# SCH_DroneSlider_Circuit.net
KiCad netlist of a schematic drawn in EasyEDA
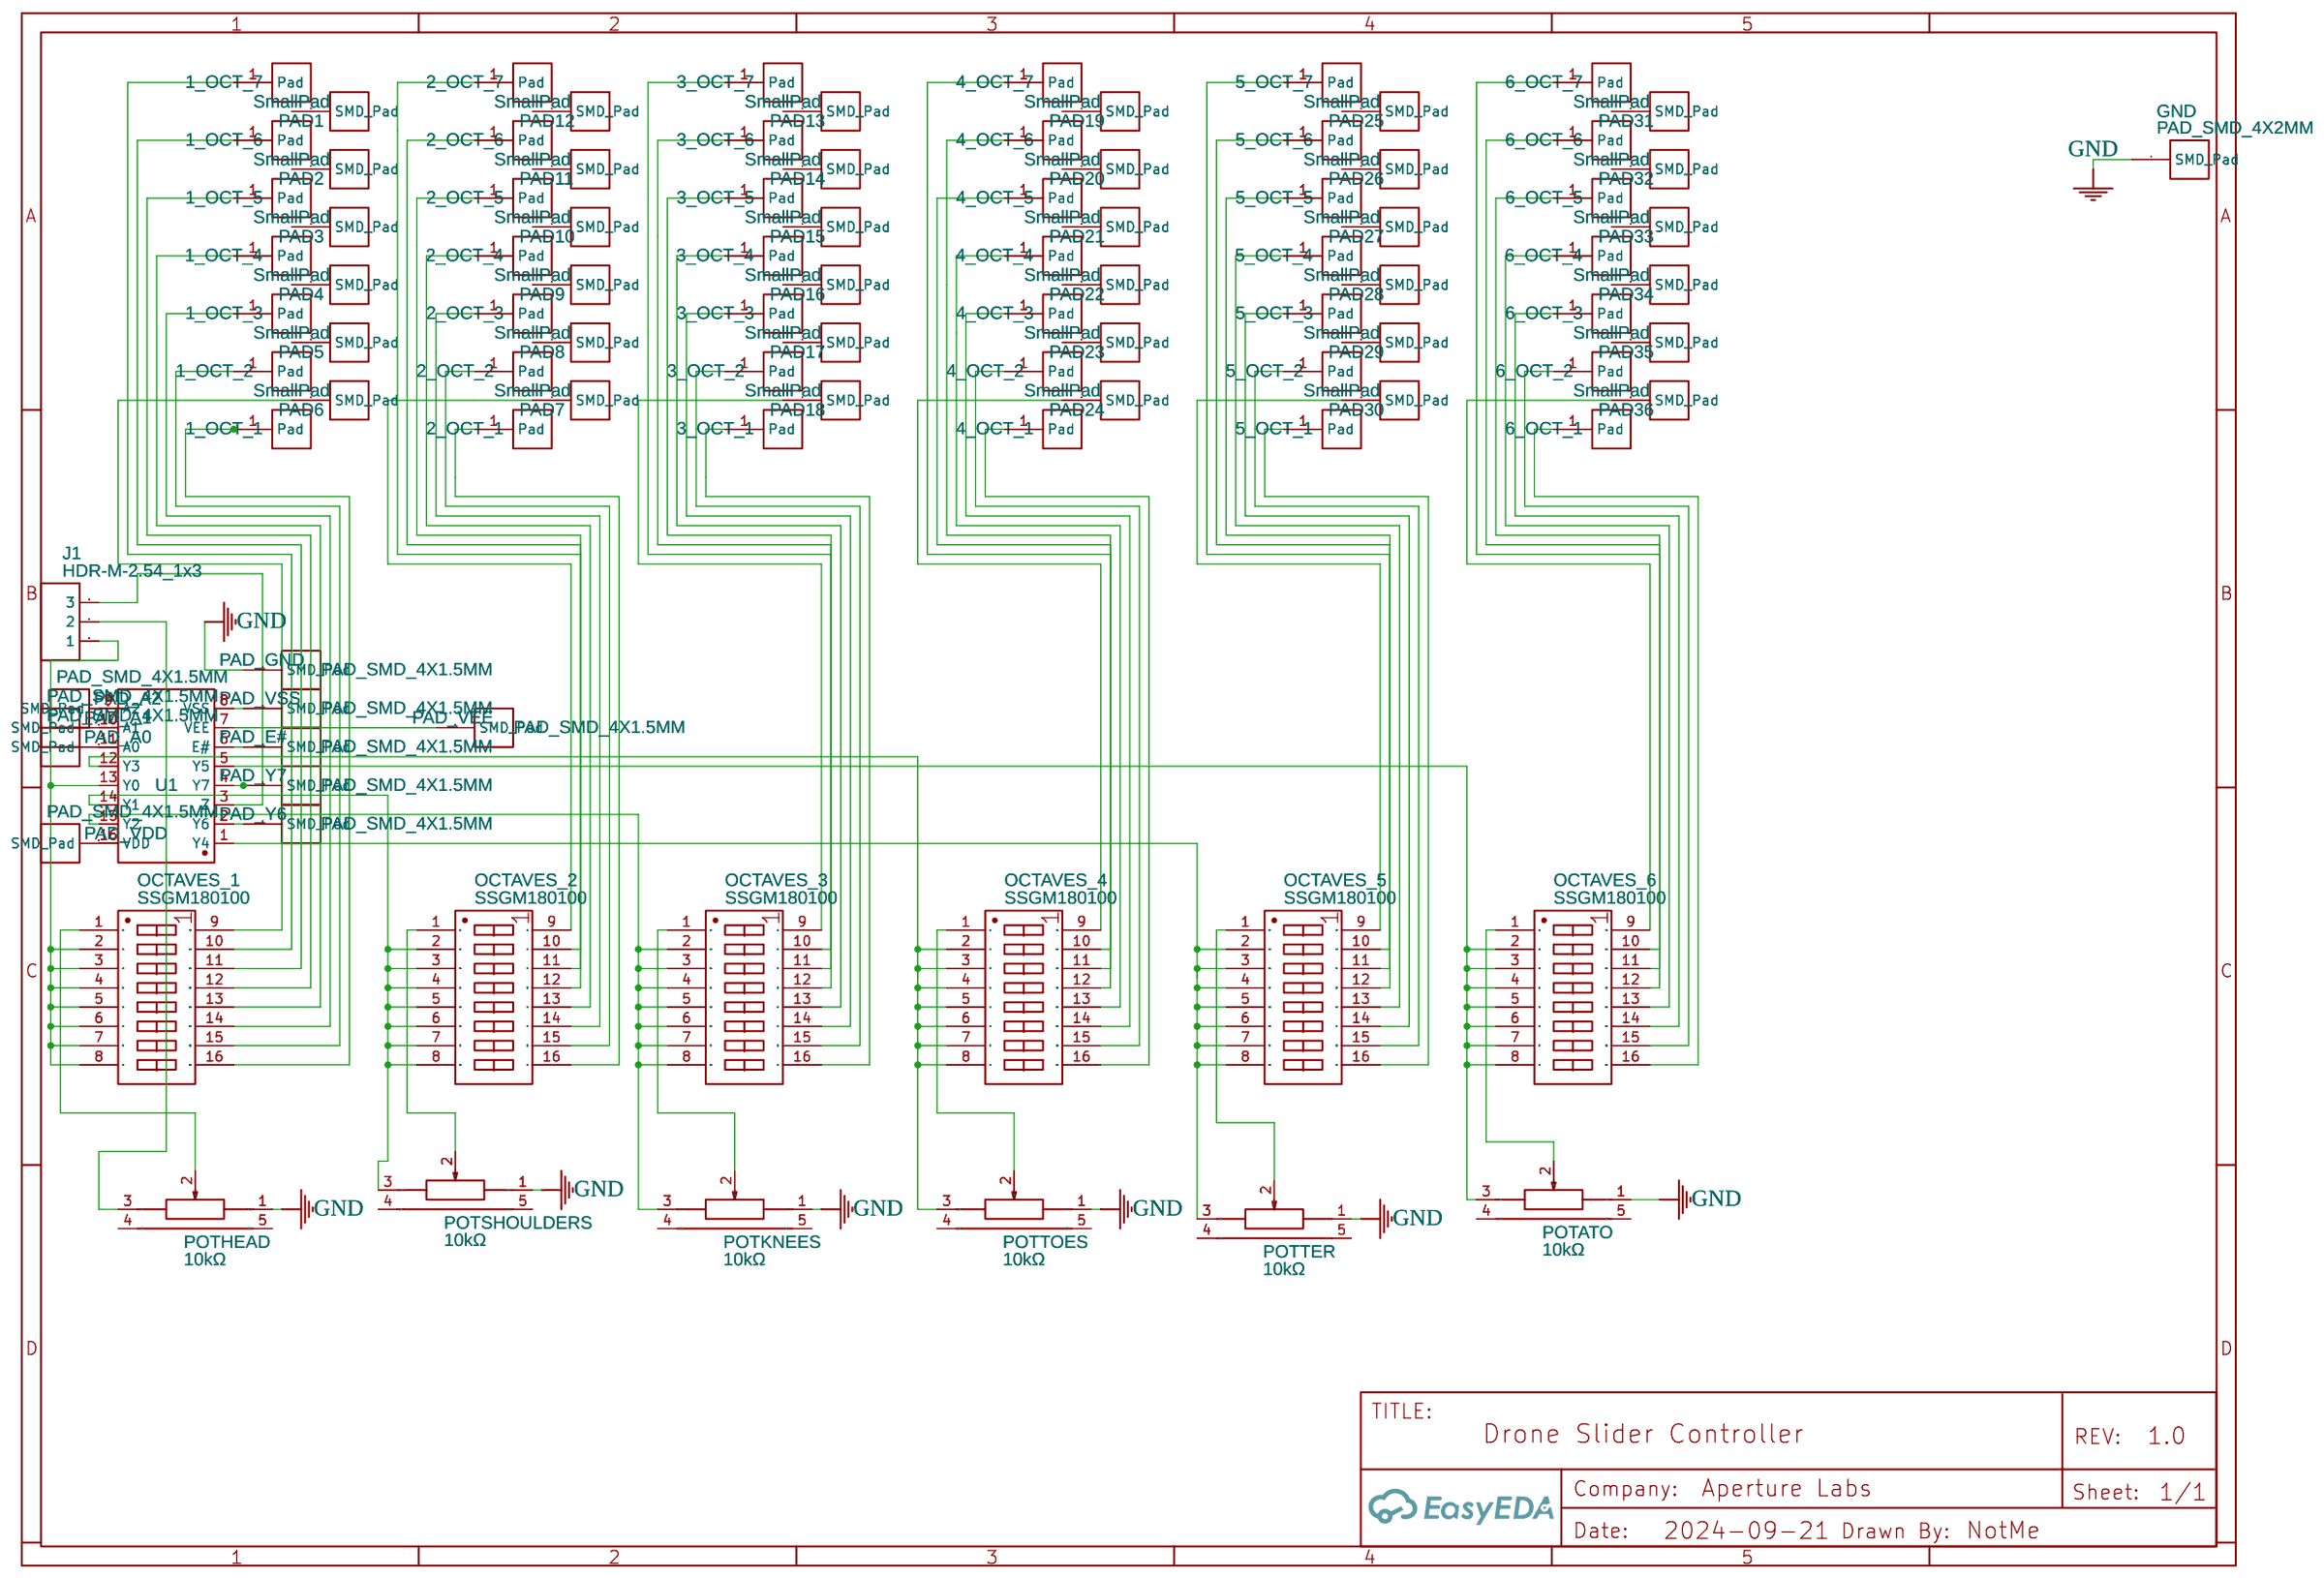
[diagram p0: schematic sheet]

(export (version "E")
  (design (tool "Eeschema 10.0.6"))
  (components
    (comp (ref "1_OCT_1") (value "OCT") (libsource (lib "") (part "PAD_5")))
    (comp (ref "1_OCT_2") (value "OCT") (libsource (lib "") (part "PAD_5")))
    (comp (ref "1_OCT_3") (value "OCT") (libsource (lib "") (part "PAD_5")))
    (comp (ref "1_OCT_4") (value "OCT") (libsource (lib "") (part "PAD_5")))
    (comp (ref "1_OCT_5") (value "OCT") (libsource (lib "") (part "PAD_5")))
    (comp (ref "1_OCT_6") (value "OCT") (libsource (lib "") (part "PAD_5")))
    (comp (ref "1_OCT_7") (value "OCT") (libsource (lib "") (part "PAD_5")))
    (comp (ref "2_OCT_1") (value "OCT") (libsource (lib "") (part "PAD_2")))
    (comp (ref "2_OCT_2") (value "OCT") (libsource (lib "") (part "PAD_2")))
    (comp (ref "2_OCT_3") (value "OCT") (libsource (lib "") (part "PAD_2")))
    (comp (ref "2_OCT_4") (value "OCT") (libsource (lib "") (part "PAD_2")))
    (comp (ref "2_OCT_5") (value "OCT") (libsource (lib "") (part "PAD_2")))
    (comp (ref "2_OCT_6") (value "OCT") (libsource (lib "") (part "PAD_2")))
    (comp (ref "2_OCT_7") (value "OCT") (libsource (lib "") (part "PAD_2")))
    (comp (ref "3_OCT_1") (value "OCT") (libsource (lib "") (part "PAD_3")))
    (comp (ref "3_OCT_2") (value "OCT") (libsource (lib "") (part "PAD_3")))
    (comp (ref "3_OCT_3") (value "OCT") (libsource (lib "") (part "PAD_3")))
    (comp (ref "3_OCT_4") (value "OCT") (libsource (lib "") (part "PAD_3")))
    (comp (ref "3_OCT_5") (value "OCT") (libsource (lib "") (part "PAD_3")))
    (comp (ref "3_OCT_6") (value "OCT") (libsource (lib "") (part "PAD_3")))
    (comp (ref "3_OCT_7") (value "OCT") (libsource (lib "") (part "PAD_3")))
    (comp (ref "4_OCT_1") (value "OCT") (libsource (lib "") (part "PAD_4")))
    (comp (ref "4_OCT_2") (value "OCT") (libsource (lib "") (part "PAD_4")))
    (comp (ref "4_OCT_3") (value "OCT") (libsource (lib "") (part "PAD_4")))
    (comp (ref "4_OCT_4") (value "OCT") (libsource (lib "") (part "PAD_4")))
    (comp (ref "4_OCT_5") (value "OCT") (libsource (lib "") (part "PAD_4")))
    (comp (ref "4_OCT_6") (value "OCT") (libsource (lib "") (part "PAD_4")))
    (comp (ref "4_OCT_7") (value "OCT") (libsource (lib "") (part "PAD_4")))
    (comp (ref "5_OCT_1") (value "OCT") (libsource (lib "") (part "PAD")))
    (comp (ref "5_OCT_2") (value "OCT") (libsource (lib "") (part "PAD")))
    (comp (ref "5_OCT_3") (value "OCT") (libsource (lib "") (part "PAD")))
    (comp (ref "5_OCT_4") (value "OCT") (libsource (lib "") (part "PAD")))
    (comp (ref "5_OCT_5") (value "OCT") (libsource (lib "") (part "PAD")))
    (comp (ref "5_OCT_6") (value "OCT") (libsource (lib "") (part "PAD")))
    (comp (ref "5_OCT_7") (value "OCT") (libsource (lib "") (part "PAD")))
    (comp (ref "6_OCT_1") (value "OCT") (libsource (lib "") (part "PAD_1")))
    (comp (ref "6_OCT_2") (value "OCT") (libsource (lib "") (part "PAD_1")))
    (comp (ref "6_OCT_3") (value "OCT") (libsource (lib "") (part "PAD_1")))
    (comp (ref "6_OCT_4") (value "OCT") (libsource (lib "") (part "PAD_1")))
    (comp (ref "6_OCT_5") (value "OCT") (libsource (lib "") (part "PAD_1")))
    (comp (ref "6_OCT_6") (value "OCT") (libsource (lib "") (part "PAD_1")))
    (comp (ref "6_OCT_7") (value "OCT") (libsource (lib "") (part "PAD_1")))
    (comp (ref "GND") (value "PAD_SMD_4X2MM") (libsource (lib "") (part "PAD_SMD_4X2MM")))
    (comp (ref "J1") (value "HDR-M-2.54_1x3") (libsource (lib "") (part "HDR-M-2.54_1x3")))
    (comp (ref "OCTAVES_1")
      (value "SSGM180100")
      (fields (field (name "Manufacturer") "ALPSALPINE(阿尔卑斯阿尔派)"))
      (libsource (lib "") (part "SSGM180100"))
    )
    (comp (ref "OCTAVES_2")
      (value "SSGM180100")
      (fields (field (name "Manufacturer") "ALPSALPINE(阿尔卑斯阿尔派)"))
      (libsource (lib "") (part "SSGM180100"))
    )
    (comp (ref "OCTAVES_3")
      (value "SSGM180100")
      (fields (field (name "Manufacturer") "ALPSALPINE(阿尔卑斯阿尔派)"))
      (libsource (lib "") (part "SSGM180100"))
    )
    (comp (ref "OCTAVES_4")
      (value "SSGM180100")
      (fields (field (name "Manufacturer") "ALPSALPINE(阿尔卑斯阿尔派)"))
      (libsource (lib "") (part "SSGM180100"))
    )
    (comp (ref "OCTAVES_5")
      (value "SSGM180100")
      (fields (field (name "Manufacturer") "ALPSALPINE(阿尔卑斯阿尔派)"))
      (libsource (lib "") (part "SSGM180100"))
    )
    (comp (ref "OCTAVES_6")
      (value "SSGM180100")
      (fields (field (name "Manufacturer") "ALPSALPINE(阿尔卑斯阿尔派)"))
      (libsource (lib "") (part "SSGM180100"))
    )
    (comp (ref "PAD1") (value "SmallPad") (libsource (lib "") (part "PAD_SMD_4X1.5MM")))
    (comp (ref "PAD2") (value "SmallPad") (libsource (lib "") (part "PAD_SMD_4X1.5MM")))
    (comp (ref "PAD3") (value "SmallPad") (libsource (lib "") (part "PAD_SMD_4X1.5MM")))
    (comp (ref "PAD4") (value "SmallPad") (libsource (lib "") (part "PAD_SMD_4X1.5MM")))
    (comp (ref "PAD5") (value "SmallPad") (libsource (lib "") (part "PAD_SMD_4X1.5MM")))
    (comp (ref "PAD6") (value "SmallPad") (libsource (lib "") (part "PAD_SMD_4X1.5MM")))
    (comp (ref "PAD7") (value "SmallPad") (libsource (lib "") (part "PAD_SMD_4X1.5MM")))
    (comp (ref "PAD8") (value "SmallPad") (libsource (lib "") (part "PAD_SMD_4X1.5MM")))
    (comp (ref "PAD9") (value "SmallPad") (libsource (lib "") (part "PAD_SMD_4X1.5MM")))
    (comp (ref "PAD10") (value "SmallPad") (libsource (lib "") (part "PAD_SMD_4X1.5MM")))
    (comp (ref "PAD11") (value "SmallPad") (libsource (lib "") (part "PAD_SMD_4X1.5MM")))
    (comp (ref "PAD12") (value "SmallPad") (libsource (lib "") (part "PAD_SMD_4X1.5MM")))
    (comp (ref "PAD13") (value "SmallPad") (libsource (lib "") (part "PAD_SMD_4X1.5MM")))
    (comp (ref "PAD14") (value "SmallPad") (libsource (lib "") (part "PAD_SMD_4X1.5MM")))
    (comp (ref "PAD15") (value "SmallPad") (libsource (lib "") (part "PAD_SMD_4X1.5MM")))
    (comp (ref "PAD16") (value "SmallPad") (libsource (lib "") (part "PAD_SMD_4X1.5MM")))
    (comp (ref "PAD17") (value "SmallPad") (libsource (lib "") (part "PAD_SMD_4X1.5MM")))
    (comp (ref "PAD18") (value "SmallPad") (libsource (lib "") (part "PAD_SMD_4X1.5MM")))
    (comp (ref "PAD19") (value "SmallPad") (libsource (lib "") (part "PAD_SMD_4X1.5MM")))
    (comp (ref "PAD20") (value "SmallPad") (libsource (lib "") (part "PAD_SMD_4X1.5MM")))
    (comp (ref "PAD21") (value "SmallPad") (libsource (lib "") (part "PAD_SMD_4X1.5MM")))
    (comp (ref "PAD22") (value "SmallPad") (libsource (lib "") (part "PAD_SMD_4X1.5MM")))
    (comp (ref "PAD23") (value "SmallPad") (libsource (lib "") (part "PAD_SMD_4X1.5MM")))
    (comp (ref "PAD24") (value "SmallPad") (libsource (lib "") (part "PAD_SMD_4X1.5MM")))
    (comp (ref "PAD25") (value "SmallPad") (libsource (lib "") (part "PAD_SMD_4X1.5MM")))
    (comp (ref "PAD26") (value "SmallPad") (libsource (lib "") (part "PAD_SMD_4X1.5MM")))
    (comp (ref "PAD27") (value "SmallPad") (libsource (lib "") (part "PAD_SMD_4X1.5MM")))
    (comp (ref "PAD28") (value "SmallPad") (libsource (lib "") (part "PAD_SMD_4X1.5MM")))
    (comp (ref "PAD29") (value "SmallPad") (libsource (lib "") (part "PAD_SMD_4X1.5MM")))
    (comp (ref "PAD30") (value "SmallPad") (libsource (lib "") (part "PAD_SMD_4X1.5MM")))
    (comp (ref "PAD31") (value "SmallPad") (libsource (lib "") (part "PAD_SMD_4X1.5MM")))
    (comp (ref "PAD32") (value "SmallPad") (libsource (lib "") (part "PAD_SMD_4X1.5MM")))
    (comp (ref "PAD33") (value "SmallPad") (libsource (lib "") (part "PAD_SMD_4X1.5MM")))
    (comp (ref "PAD34") (value "SmallPad") (libsource (lib "") (part "PAD_SMD_4X1.5MM")))
    (comp (ref "PAD35") (value "SmallPad") (libsource (lib "") (part "PAD_SMD_4X1.5MM")))
    (comp (ref "PAD36") (value "SmallPad") (libsource (lib "") (part "PAD_SMD_4X1.5MM")))
    (comp (ref "PAD_A0") (value "PAD_SMD_4X1.5MM") (libsource (lib "") (part "PAD_SMD_4X1.5MM_2")))
    (comp (ref "PAD_A1") (value "PAD_SMD_4X1.5MM") (libsource (lib "") (part "PAD_SMD_4X1.5MM_2")))
    (comp (ref "PAD_A2") (value "PAD_SMD_4X1.5MM") (libsource (lib "") (part "PAD_SMD_4X1.5MM_2")))
    (comp (ref "PAD_E#") (value "PAD_SMD_4X1.5MM") (libsource (lib "") (part "PAD_SMD_4X1.5MM_1")))
    (comp (ref "PAD_GND") (value "PAD_SMD_4X1.5MM") (libsource (lib "") (part "PAD_SMD_4X1.5MM_4")))
    (comp (ref "PAD_VDD") (value "PAD_SMD_4X1.5MM") (libsource (lib "") (part "PAD_SMD_4X1.5MM_7")))
    (comp (ref "PAD_VEE") (value "PAD_SMD_4X1.5MM") (libsource (lib "") (part "PAD_SMD_4X1.5MM_6")))
    (comp (ref "PAD_VSS") (value "PAD_SMD_4X1.5MM") (libsource (lib "") (part "PAD_SMD_4X1.5MM_5")))
    (comp (ref "PAD_Y6") (value "PAD_SMD_4X1.5MM") (libsource (lib "") (part "PAD_SMD_4X1.5MM_3")))
    (comp (ref "PAD_Y7") (value "PAD_SMD_4X1.5MM") (libsource (lib "") (part "PAD_SMD_4X1.5MM_3")))
    (comp (ref "POTATO")
      (value "10kΩ")
      (fields
        (field (name "Manufacturer Part") "RK09K1130A5R")
        (field (name "Manufacturer") "ALPSALPINE(阿尔卑斯阿尔派)")
      )
      (libsource (lib "") (part "RK09K1130A5R_1"))
    )
    (comp (ref "POTHEAD")
      (value "10kΩ")
      (fields
        (field (name "Manufacturer Part") "RK09K1130A5R")
        (field (name "Manufacturer") "ALPSALPINE(阿尔卑斯阿尔派)")
      )
      (libsource (lib "") (part "RK09K1130A5R_2"))
    )
    (comp (ref "POTKNEES")
      (value "10kΩ")
      (fields
        (field (name "Manufacturer Part") "RK09K1130A5R")
        (field (name "Manufacturer") "ALPSALPINE(阿尔卑斯阿尔派)")
      )
      (libsource (lib "") (part "RK09K1130A5R"))
    )
    (comp (ref "POTSHOULDERS")
      (value "10kΩ")
      (fields
        (field (name "Manufacturer Part") "RK09K1130A5R")
        (field (name "Manufacturer") "ALPSALPINE(阿尔卑斯阿尔派)")
      )
      (libsource (lib "") (part "RK09K1130A5R_3"))
    )
    (comp (ref "POTTER")
      (value "10kΩ")
      (fields
        (field (name "Manufacturer Part") "RK09K1130A5R")
        (field (name "Manufacturer") "ALPSALPINE(阿尔卑斯阿尔派)")
      )
      (libsource (lib "") (part "RK09K1130A5R_4"))
    )
    (comp (ref "POTTOES")
      (value "10kΩ")
      (fields
        (field (name "Manufacturer Part") "RK09K1130A5R")
        (field (name "Manufacturer") "ALPSALPINE(阿尔卑斯阿尔派)")
      )
      (libsource (lib "") (part "RK09K1130A5R_5"))
    )
    (comp (ref "U1")
      (value "CD4051BE_C507164")
      (fields (field (name "Manufacturer Part") "CD4051BE") (field (name "Manufacturer") "HGSEMI(华冠)"))
      (libsource (lib "") (part "CD4051BE_C507164"))
    )
  )
  (nets
    (net (code "1") (name "GND") (class "Default")
      (node (ref "GND") (pin "1") (pinfunction "SMD_Pad_1") (pintype "unspecified"))
      (node (ref "PAD_GND") (pin "1") (pinfunction "SMD_Pad_1") (pintype "unspecified"))
      (node (ref "POTATO") (pin "1") (pinfunction "1_1") (pintype "unspecified"))
      (node (ref "POTHEAD") (pin "1") (pinfunction "1_1") (pintype "unspecified"))
      (node (ref "POTKNEES") (pin "1") (pinfunction "1_1") (pintype "unspecified"))
      (node (ref "POTSHOULDERS") (pin "1") (pinfunction "1_1") (pintype "unspecified"))
      (node (ref "POTTER") (pin "1") (pinfunction "1_1") (pintype "unspecified"))
      (node (ref "POTTOES") (pin "1") (pinfunction "1_1") (pintype "unspecified"))
    )
    (net (code "2") (name "Net-(1_OCT_1-Pad)") (class "Default")
      (node (ref "1_OCT_1") (pin "1") (pinfunction "Pad_1") (pintype "unspecified"))
      (node (ref "OCTAVES_1") (pin "16") (pinfunction "PIN16_16") (pintype "unspecified"))
    )
    (net (code "3") (name "Net-(1_OCT_2-Pad)") (class "Default")
      (node (ref "1_OCT_2") (pin "1") (pinfunction "Pad_1") (pintype "unspecified"))
      (node (ref "OCTAVES_1") (pin "15") (pinfunction "PIN16_15") (pintype "unspecified"))
    )
    (net (code "4") (name "Net-(2_OCT_1-Pad)") (class "Default")
      (node (ref "2_OCT_1") (pin "1") (pinfunction "Pad_1") (pintype "unspecified"))
      (node (ref "OCTAVES_2") (pin "16") (pinfunction "PIN16_16") (pintype "unspecified"))
    )
    (net (code "5") (name "Net-(2_OCT_2-Pad)") (class "Default")
      (node (ref "2_OCT_2") (pin "1") (pinfunction "Pad_1") (pintype "unspecified"))
      (node (ref "OCTAVES_2") (pin "15") (pinfunction "PIN16_15") (pintype "unspecified"))
    )
    (net (code "6") (name "Net-(3_OCT_1-Pad)") (class "Default")
      (node (ref "3_OCT_1") (pin "1") (pinfunction "Pad_1") (pintype "unspecified"))
      (node (ref "OCTAVES_3") (pin "16") (pinfunction "PIN16_16") (pintype "unspecified"))
    )
    (net (code "7") (name "Net-(3_OCT_2-Pad)") (class "Default")
      (node (ref "3_OCT_2") (pin "1") (pinfunction "Pad_1") (pintype "unspecified"))
      (node (ref "OCTAVES_3") (pin "15") (pinfunction "PIN16_15") (pintype "unspecified"))
    )
    (net (code "8") (name "Net-(4_OCT_1-Pad)") (class "Default")
      (node (ref "4_OCT_1") (pin "1") (pinfunction "Pad_1") (pintype "unspecified"))
      (node (ref "OCTAVES_4") (pin "16") (pinfunction "PIN16_16") (pintype "unspecified"))
    )
    (net (code "9") (name "Net-(4_OCT_2-Pad)") (class "Default")
      (node (ref "4_OCT_2") (pin "1") (pinfunction "Pad_1") (pintype "unspecified"))
      (node (ref "OCTAVES_4") (pin "15") (pinfunction "PIN16_15") (pintype "unspecified"))
    )
    (net (code "10") (name "Net-(5_OCT_1-Pad)") (class "Default")
      (node (ref "5_OCT_1") (pin "1") (pinfunction "Pad_1") (pintype "unspecified"))
      (node (ref "OCTAVES_5") (pin "16") (pinfunction "PIN16_16") (pintype "unspecified"))
    )
    (net (code "11") (name "Net-(5_OCT_2-Pad)") (class "Default")
      (node (ref "5_OCT_2") (pin "1") (pinfunction "Pad_1") (pintype "unspecified"))
      (node (ref "OCTAVES_5") (pin "15") (pinfunction "PIN16_15") (pintype "unspecified"))
    )
    (net (code "12") (name "Net-(6_OCT_1-Pad)") (class "Default")
      (node (ref "6_OCT_1") (pin "1") (pinfunction "Pad_1") (pintype "unspecified"))
      (node (ref "OCTAVES_6") (pin "16") (pinfunction "PIN16_16") (pintype "unspecified"))
    )
    (net (code "13") (name "Net-(6_OCT_2-Pad)") (class "Default")
      (node (ref "6_OCT_2") (pin "1") (pinfunction "Pad_1") (pintype "unspecified"))
      (node (ref "OCTAVES_6") (pin "15") (pinfunction "PIN16_15") (pintype "unspecified"))
    )
    (net (code "14") (name "Net-(J1-Pad2)") (class "Default")
      (node (ref "J1") (pin "2") (pinfunction "2_2") (pintype "input"))
      (node (ref "POTHEAD") (pin "3") (pinfunction "3_3") (pintype "unspecified"))
    )
    (net (code "15") (name "Net-(OCTAVES_1-PIN1)") (class "Default")
      (node (ref "OCTAVES_1") (pin "1") (pinfunction "PIN1_1") (pintype "unspecified"))
      (node (ref "POTHEAD") (pin "2") (pinfunction "2_2") (pintype "unspecified"))
    )
    (net (code "16") (name "Net-(OCTAVES_1-PIN2)") (class "Default")
      (node (ref "J1") (pin "1") (pinfunction "1_1") (pintype "input"))
      (node (ref "OCTAVES_1") (pin "2") (pinfunction "PIN2_2") (pintype "unspecified"))
      (node (ref "OCTAVES_1") (pin "3") (pinfunction "PIN3_3") (pintype "unspecified"))
      (node (ref "OCTAVES_1") (pin "4") (pinfunction "PIN4_4") (pintype "unspecified"))
      (node (ref "OCTAVES_1") (pin "5") (pinfunction "PIN5_5") (pintype "unspecified"))
      (node (ref "OCTAVES_1") (pin "6") (pinfunction "PIN6_6") (pintype "unspecified"))
      (node (ref "OCTAVES_1") (pin "7") (pinfunction "PIN7_7") (pintype "unspecified"))
      (node (ref "OCTAVES_1") (pin "8") (pinfunction "PIN8_8") (pintype "unspecified"))
      (node (ref "U1") (pin "13") (pinfunction "Y0_13") (pintype "unspecified"))
    )
    (net (code "17") (name "Net-(OCTAVES_1-PIN9)") (class "Default")
      (node (ref "OCTAVES_1") (pin "9") (pinfunction "PIN9_9") (pintype "unspecified"))
      (node (ref "PAD6") (pin "1") (pinfunction "SMD_Pad_1") (pintype "unspecified"))
    )
    (net (code "18") (name "Net-(OCTAVES_1-PIN10)") (class "Default")
      (node (ref "1_OCT_7") (pin "1") (pinfunction "Pad_1") (pintype "unspecified"))
      (node (ref "OCTAVES_1") (pin "10") (pinfunction "PIN10_10") (pintype "unspecified"))
    )
    (net (code "19") (name "Net-(OCTAVES_1-PIN11)") (class "Default")
      (node (ref "1_OCT_6") (pin "1") (pinfunction "Pad_1") (pintype "unspecified"))
      (node (ref "OCTAVES_1") (pin "11") (pinfunction "PIN11_11") (pintype "unspecified"))
    )
    (net (code "20") (name "Net-(OCTAVES_1-PIN12)") (class "Default")
      (node (ref "1_OCT_5") (pin "1") (pinfunction "Pad_1") (pintype "unspecified"))
      (node (ref "OCTAVES_1") (pin "12") (pinfunction "PIN12_12") (pintype "unspecified"))
    )
    (net (code "21") (name "Net-(OCTAVES_1-PIN13)") (class "Default")
      (node (ref "1_OCT_4") (pin "1") (pinfunction "Pad_1") (pintype "unspecified"))
      (node (ref "OCTAVES_1") (pin "13") (pinfunction "PIN13_13") (pintype "unspecified"))
    )
    (net (code "22") (name "Net-(OCTAVES_1-PIN14)") (class "Default")
      (node (ref "1_OCT_3") (pin "1") (pinfunction "Pad_1") (pintype "unspecified"))
      (node (ref "OCTAVES_1") (pin "14") (pinfunction "PIN14_14") (pintype "unspecified"))
    )
    (net (code "23") (name "Net-(OCTAVES_2-PIN1)") (class "Default")
      (node (ref "OCTAVES_2") (pin "1") (pinfunction "PIN1_1") (pintype "unspecified"))
      (node (ref "POTSHOULDERS") (pin "2") (pinfunction "2_2") (pintype "unspecified"))
    )
    (net (code "24") (name "Net-(OCTAVES_2-PIN2)") (class "Default")
      (node (ref "OCTAVES_2") (pin "2") (pinfunction "PIN2_2") (pintype "unspecified"))
      (node (ref "OCTAVES_2") (pin "3") (pinfunction "PIN3_3") (pintype "unspecified"))
      (node (ref "OCTAVES_2") (pin "4") (pinfunction "PIN4_4") (pintype "unspecified"))
      (node (ref "OCTAVES_2") (pin "5") (pinfunction "PIN5_5") (pintype "unspecified"))
      (node (ref "OCTAVES_2") (pin "6") (pinfunction "PIN6_6") (pintype "unspecified"))
      (node (ref "OCTAVES_2") (pin "7") (pinfunction "PIN7_7") (pintype "unspecified"))
      (node (ref "OCTAVES_2") (pin "8") (pinfunction "PIN8_8") (pintype "unspecified"))
      (node (ref "POTSHOULDERS") (pin "3") (pinfunction "3_3") (pintype "unspecified"))
      (node (ref "U1") (pin "14") (pinfunction "Y1_14") (pintype "unspecified"))
    )
    (net (code "25") (name "Net-(OCTAVES_2-PIN9)") (class "Default")
      (node (ref "OCTAVES_2") (pin "9") (pinfunction "PIN9_9") (pintype "unspecified"))
      (node (ref "PAD7") (pin "1") (pinfunction "SMD_Pad_1") (pintype "unspecified"))
    )
    (net (code "26") (name "Net-(OCTAVES_2-PIN10)") (class "Default")
      (node (ref "2_OCT_7") (pin "1") (pinfunction "Pad_1") (pintype "unspecified"))
      (node (ref "OCTAVES_2") (pin "10") (pinfunction "PIN10_10") (pintype "unspecified"))
    )
    (net (code "27") (name "Net-(OCTAVES_2-PIN11)") (class "Default")
      (node (ref "2_OCT_6") (pin "1") (pinfunction "Pad_1") (pintype "unspecified"))
      (node (ref "OCTAVES_2") (pin "11") (pinfunction "PIN11_11") (pintype "unspecified"))
    )
    (net (code "28") (name "Net-(OCTAVES_2-PIN12)") (class "Default")
      (node (ref "2_OCT_5") (pin "1") (pinfunction "Pad_1") (pintype "unspecified"))
      (node (ref "OCTAVES_2") (pin "12") (pinfunction "PIN12_12") (pintype "unspecified"))
    )
    (net (code "29") (name "Net-(OCTAVES_2-PIN13)") (class "Default")
      (node (ref "2_OCT_4") (pin "1") (pinfunction "Pad_1") (pintype "unspecified"))
      (node (ref "OCTAVES_2") (pin "13") (pinfunction "PIN13_13") (pintype "unspecified"))
    )
    (net (code "30") (name "Net-(OCTAVES_2-PIN14)") (class "Default")
      (node (ref "2_OCT_3") (pin "1") (pinfunction "Pad_1") (pintype "unspecified"))
      (node (ref "OCTAVES_2") (pin "14") (pinfunction "PIN14_14") (pintype "unspecified"))
    )
    (net (code "31") (name "Net-(OCTAVES_3-PIN1)") (class "Default")
      (node (ref "OCTAVES_3") (pin "1") (pinfunction "PIN1_1") (pintype "unspecified"))
      (node (ref "POTKNEES") (pin "2") (pinfunction "2_2") (pintype "unspecified"))
    )
    (net (code "32") (name "Net-(OCTAVES_3-PIN2)") (class "Default")
      (node (ref "OCTAVES_3") (pin "2") (pinfunction "PIN2_2") (pintype "unspecified"))
      (node (ref "OCTAVES_3") (pin "3") (pinfunction "PIN3_3") (pintype "unspecified"))
      (node (ref "OCTAVES_3") (pin "4") (pinfunction "PIN4_4") (pintype "unspecified"))
      (node (ref "OCTAVES_3") (pin "5") (pinfunction "PIN5_5") (pintype "unspecified"))
      (node (ref "OCTAVES_3") (pin "6") (pinfunction "PIN6_6") (pintype "unspecified"))
      (node (ref "OCTAVES_3") (pin "7") (pinfunction "PIN7_7") (pintype "unspecified"))
      (node (ref "OCTAVES_3") (pin "8") (pinfunction "PIN8_8") (pintype "unspecified"))
      (node (ref "POTKNEES") (pin "3") (pinfunction "3_3") (pintype "unspecified"))
      (node (ref "U1") (pin "15") (pinfunction "Y2_15") (pintype "unspecified"))
    )
    (net (code "33") (name "Net-(OCTAVES_3-PIN9)") (class "Default")
      (node (ref "OCTAVES_3") (pin "9") (pinfunction "PIN9_9") (pintype "unspecified"))
      (node (ref "PAD18") (pin "1") (pinfunction "SMD_Pad_1") (pintype "unspecified"))
    )
    (net (code "34") (name "Net-(OCTAVES_3-PIN10)") (class "Default")
      (node (ref "3_OCT_7") (pin "1") (pinfunction "Pad_1") (pintype "unspecified"))
      (node (ref "OCTAVES_3") (pin "10") (pinfunction "PIN10_10") (pintype "unspecified"))
    )
    (net (code "35") (name "Net-(OCTAVES_3-PIN11)") (class "Default")
      (node (ref "3_OCT_6") (pin "1") (pinfunction "Pad_1") (pintype "unspecified"))
      (node (ref "OCTAVES_3") (pin "11") (pinfunction "PIN11_11") (pintype "unspecified"))
    )
    (net (code "36") (name "Net-(OCTAVES_3-PIN12)") (class "Default")
      (node (ref "3_OCT_5") (pin "1") (pinfunction "Pad_1") (pintype "unspecified"))
      (node (ref "OCTAVES_3") (pin "12") (pinfunction "PIN12_12") (pintype "unspecified"))
    )
    (net (code "37") (name "Net-(OCTAVES_3-PIN13)") (class "Default")
      (node (ref "3_OCT_4") (pin "1") (pinfunction "Pad_1") (pintype "unspecified"))
      (node (ref "OCTAVES_3") (pin "13") (pinfunction "PIN13_13") (pintype "unspecified"))
    )
    (net (code "38") (name "Net-(OCTAVES_3-PIN14)") (class "Default")
      (node (ref "3_OCT_3") (pin "1") (pinfunction "Pad_1") (pintype "unspecified"))
      (node (ref "OCTAVES_3") (pin "14") (pinfunction "PIN14_14") (pintype "unspecified"))
    )
    (net (code "39") (name "Net-(OCTAVES_4-PIN1)") (class "Default")
      (node (ref "OCTAVES_4") (pin "1") (pinfunction "PIN1_1") (pintype "unspecified"))
      (node (ref "POTTOES") (pin "2") (pinfunction "2_2") (pintype "unspecified"))
    )
    (net (code "40") (name "Net-(OCTAVES_4-PIN2)") (class "Default")
      (node (ref "OCTAVES_4") (pin "2") (pinfunction "PIN2_2") (pintype "unspecified"))
      (node (ref "OCTAVES_4") (pin "3") (pinfunction "PIN3_3") (pintype "unspecified"))
      (node (ref "OCTAVES_4") (pin "4") (pinfunction "PIN4_4") (pintype "unspecified"))
      (node (ref "OCTAVES_4") (pin "5") (pinfunction "PIN5_5") (pintype "unspecified"))
      (node (ref "OCTAVES_4") (pin "6") (pinfunction "PIN6_6") (pintype "unspecified"))
      (node (ref "OCTAVES_4") (pin "7") (pinfunction "PIN7_7") (pintype "unspecified"))
      (node (ref "OCTAVES_4") (pin "8") (pinfunction "PIN8_8") (pintype "unspecified"))
      (node (ref "POTTOES") (pin "3") (pinfunction "3_3") (pintype "unspecified"))
      (node (ref "U1") (pin "12") (pinfunction "Y3_12") (pintype "unspecified"))
    )
    (net (code "41") (name "Net-(OCTAVES_4-PIN9)") (class "Default")
      (node (ref "OCTAVES_4") (pin "9") (pinfunction "PIN9_9") (pintype "unspecified"))
      (node (ref "PAD24") (pin "1") (pinfunction "SMD_Pad_1") (pintype "unspecified"))
    )
    (net (code "42") (name "Net-(OCTAVES_4-PIN10)") (class "Default")
      (node (ref "4_OCT_7") (pin "1") (pinfunction "Pad_1") (pintype "unspecified"))
      (node (ref "OCTAVES_4") (pin "10") (pinfunction "PIN10_10") (pintype "unspecified"))
    )
    (net (code "43") (name "Net-(OCTAVES_4-PIN11)") (class "Default")
      (node (ref "4_OCT_5") (pin "1") (pinfunction "Pad_1") (pintype "unspecified"))
      (node (ref "OCTAVES_4") (pin "11") (pinfunction "PIN11_11") (pintype "unspecified"))
    )
    (net (code "44") (name "Net-(OCTAVES_4-PIN12)") (class "Default")
      (node (ref "4_OCT_6") (pin "1") (pinfunction "Pad_1") (pintype "unspecified"))
      (node (ref "OCTAVES_4") (pin "12") (pinfunction "PIN12_12") (pintype "unspecified"))
    )
    (net (code "45") (name "Net-(OCTAVES_4-PIN13)") (class "Default")
      (node (ref "4_OCT_4") (pin "1") (pinfunction "Pad_1") (pintype "unspecified"))
      (node (ref "OCTAVES_4") (pin "13") (pinfunction "PIN13_13") (pintype "unspecified"))
    )
    (net (code "46") (name "Net-(OCTAVES_4-PIN14)") (class "Default")
      (node (ref "4_OCT_3") (pin "1") (pinfunction "Pad_1") (pintype "unspecified"))
      (node (ref "OCTAVES_4") (pin "14") (pinfunction "PIN14_14") (pintype "unspecified"))
    )
    (net (code "47") (name "Net-(OCTAVES_5-PIN1)") (class "Default")
      (node (ref "OCTAVES_5") (pin "1") (pinfunction "PIN1_1") (pintype "unspecified"))
      (node (ref "POTTER") (pin "2") (pinfunction "2_2") (pintype "unspecified"))
    )
    (net (code "48") (name "Net-(OCTAVES_5-PIN2)") (class "Default")
      (node (ref "OCTAVES_5") (pin "2") (pinfunction "PIN2_2") (pintype "unspecified"))
      (node (ref "OCTAVES_5") (pin "3") (pinfunction "PIN3_3") (pintype "unspecified"))
      (node (ref "OCTAVES_5") (pin "4") (pinfunction "PIN4_4") (pintype "unspecified"))
      (node (ref "OCTAVES_5") (pin "5") (pinfunction "PIN5_5") (pintype "unspecified"))
      (node (ref "OCTAVES_5") (pin "6") (pinfunction "PIN6_6") (pintype "unspecified"))
      (node (ref "OCTAVES_5") (pin "7") (pinfunction "PIN7_7") (pintype "unspecified"))
      (node (ref "OCTAVES_5") (pin "8") (pinfunction "PIN8_8") (pintype "unspecified"))
      (node (ref "POTTER") (pin "3") (pinfunction "3_3") (pintype "unspecified"))
      (node (ref "U1") (pin "1") (pinfunction "Y4_1") (pintype "unspecified"))
    )
    (net (code "49") (name "Net-(OCTAVES_5-PIN9)") (class "Default")
      (node (ref "OCTAVES_5") (pin "9") (pinfunction "PIN9_9") (pintype "unspecified"))
      (node (ref "PAD30") (pin "1") (pinfunction "SMD_Pad_1") (pintype "unspecified"))
    )
    (net (code "50") (name "Net-(OCTAVES_5-PIN10)") (class "Default")
      (node (ref "5_OCT_7") (pin "1") (pinfunction "Pad_1") (pintype "unspecified"))
      (node (ref "OCTAVES_5") (pin "10") (pinfunction "PIN10_10") (pintype "unspecified"))
    )
    (net (code "51") (name "Net-(OCTAVES_5-PIN11)") (class "Default")
      (node (ref "5_OCT_6") (pin "1") (pinfunction "Pad_1") (pintype "unspecified"))
      (node (ref "OCTAVES_5") (pin "11") (pinfunction "PIN11_11") (pintype "unspecified"))
    )
    (net (code "52") (name "Net-(OCTAVES_5-PIN12)") (class "Default")
      (node (ref "5_OCT_5") (pin "1") (pinfunction "Pad_1") (pintype "unspecified"))
      (node (ref "OCTAVES_5") (pin "12") (pinfunction "PIN12_12") (pintype "unspecified"))
    )
    (net (code "53") (name "Net-(OCTAVES_5-PIN13)") (class "Default")
      (node (ref "5_OCT_4") (pin "1") (pinfunction "Pad_1") (pintype "unspecified"))
      (node (ref "OCTAVES_5") (pin "13") (pinfunction "PIN13_13") (pintype "unspecified"))
    )
    (net (code "54") (name "Net-(OCTAVES_5-PIN14)") (class "Default")
      (node (ref "5_OCT_3") (pin "1") (pinfunction "Pad_1") (pintype "unspecified"))
      (node (ref "OCTAVES_5") (pin "14") (pinfunction "PIN14_14") (pintype "unspecified"))
    )
    (net (code "55") (name "Net-(OCTAVES_6-PIN1)") (class "Default")
      (node (ref "OCTAVES_6") (pin "1") (pinfunction "PIN1_1") (pintype "unspecified"))
      (node (ref "POTATO") (pin "2") (pinfunction "2_2") (pintype "unspecified"))
    )
    (net (code "56") (name "Net-(OCTAVES_6-PIN2)") (class "Default")
      (node (ref "OCTAVES_6") (pin "2") (pinfunction "PIN2_2") (pintype "unspecified"))
      (node (ref "OCTAVES_6") (pin "3") (pinfunction "PIN3_3") (pintype "unspecified"))
      (node (ref "OCTAVES_6") (pin "4") (pinfunction "PIN4_4") (pintype "unspecified"))
      (node (ref "OCTAVES_6") (pin "5") (pinfunction "PIN5_5") (pintype "unspecified"))
      (node (ref "OCTAVES_6") (pin "6") (pinfunction "PIN6_6") (pintype "unspecified"))
      (node (ref "OCTAVES_6") (pin "7") (pinfunction "PIN7_7") (pintype "unspecified"))
      (node (ref "OCTAVES_6") (pin "8") (pinfunction "PIN8_8") (pintype "unspecified"))
      (node (ref "POTATO") (pin "3") (pinfunction "3_3") (pintype "unspecified"))
      (node (ref "U1") (pin "5") (pinfunction "Y5_5") (pintype "unspecified"))
    )
    (net (code "57") (name "Net-(OCTAVES_6-PIN9)") (class "Default")
      (node (ref "OCTAVES_6") (pin "9") (pinfunction "PIN9_9") (pintype "unspecified"))
      (node (ref "PAD36") (pin "1") (pinfunction "SMD_Pad_1") (pintype "unspecified"))
    )
    (net (code "58") (name "Net-(OCTAVES_6-PIN10)") (class "Default")
      (node (ref "6_OCT_7") (pin "1") (pinfunction "Pad_1") (pintype "unspecified"))
      (node (ref "OCTAVES_6") (pin "10") (pinfunction "PIN10_10") (pintype "unspecified"))
    )
    (net (code "59") (name "Net-(OCTAVES_6-PIN11)") (class "Default")
      (node (ref "6_OCT_6") (pin "1") (pinfunction "Pad_1") (pintype "unspecified"))
      (node (ref "OCTAVES_6") (pin "11") (pinfunction "PIN11_11") (pintype "unspecified"))
    )
    (net (code "60") (name "Net-(OCTAVES_6-PIN12)") (class "Default")
      (node (ref "6_OCT_5") (pin "1") (pinfunction "Pad_1") (pintype "unspecified"))
      (node (ref "OCTAVES_6") (pin "12") (pinfunction "PIN12_12") (pintype "unspecified"))
    )
    (net (code "61") (name "Net-(OCTAVES_6-PIN13)") (class "Default")
      (node (ref "6_OCT_4") (pin "1") (pinfunction "Pad_1") (pintype "unspecified"))
      (node (ref "OCTAVES_6") (pin "13") (pinfunction "PIN13_13") (pintype "unspecified"))
    )
    (net (code "62") (name "Net-(OCTAVES_6-PIN14)") (class "Default")
      (node (ref "6_OCT_3") (pin "1") (pinfunction "Pad_1") (pintype "unspecified"))
      (node (ref "OCTAVES_6") (pin "14") (pinfunction "PIN14_14") (pintype "unspecified"))
    )
    (net (code "63") (name "Net-(PAD_A0-SMD_Pad)") (class "Default")
      (node (ref "PAD_A0") (pin "1") (pinfunction "SMD_Pad_1") (pintype "unspecified"))
      (node (ref "U1") (pin "11") (pinfunction "A0_11") (pintype "unspecified"))
    )
    (net (code "64") (name "Net-(PAD_A1-SMD_Pad)") (class "Default")
      (node (ref "PAD_A1") (pin "1") (pinfunction "SMD_Pad_1") (pintype "unspecified"))
      (node (ref "U1") (pin "10") (pinfunction "A1_10") (pintype "unspecified"))
    )
    (net (code "65") (name "Net-(PAD_A2-SMD_Pad)") (class "Default")
      (node (ref "PAD_A2") (pin "1") (pinfunction "SMD_Pad_1") (pintype "unspecified"))
      (node (ref "U1") (pin "9") (pinfunction "A2_9") (pintype "unspecified"))
    )
    (net (code "66") (name "Net-(PAD_E#-SMD_Pad)") (class "Default")
      (node (ref "PAD_E#") (pin "1") (pinfunction "SMD_Pad_1") (pintype "unspecified"))
      (node (ref "U1") (pin "6") (pinfunction "E#_6") (pintype "unspecified"))
    )
    (net (code "67") (name "Net-(PAD_VDD-SMD_Pad)") (class "Default")
      (node (ref "PAD_VDD") (pin "1") (pinfunction "SMD_Pad_1") (pintype "unspecified"))
      (node (ref "U1") (pin "16") (pinfunction "VDD_16") (pintype "unspecified"))
    )
    (net (code "68") (name "Net-(PAD_VEE-SMD_Pad)") (class "Default")
      (node (ref "PAD_VEE") (pin "1") (pinfunction "SMD_Pad_1") (pintype "unspecified"))
      (node (ref "U1") (pin "7") (pinfunction "VEE_7") (pintype "unspecified"))
    )
    (net (code "69") (name "Net-(PAD_VSS-SMD_Pad)") (class "Default")
      (node (ref "PAD_VSS") (pin "1") (pinfunction "SMD_Pad_1") (pintype "unspecified"))
      (node (ref "U1") (pin "8") (pinfunction "VSS_8") (pintype "unspecified"))
    )
    (net (code "70") (name "Net-(PAD_Y6-SMD_Pad)") (class "Default")
      (node (ref "PAD_Y6") (pin "1") (pinfunction "SMD_Pad_1") (pintype "unspecified"))
      (node (ref "U1") (pin "2") (pinfunction "Y6_2") (pintype "unspecified"))
    )
    (net (code "71") (name "Net-(PAD_Y7-SMD_Pad)") (class "Default")
      (node (ref "PAD_Y7") (pin "1") (pinfunction "SMD_Pad_1") (pintype "unspecified"))
      (node (ref "U1") (pin "4") (pinfunction "Y7_4") (pintype "unspecified"))
    )
    (net (code "72") (name "Net-(U1-Z)") (class "Default")
      (node (ref "J1") (pin "3") (pinfunction "3_3") (pintype "input"))
      (node (ref "U1") (pin "3") (pinfunction "Z_3") (pintype "unspecified"))
    )
    (net (code "73") (name "unconnected-(PAD1-SMD_Pad-Pad1)") (class "Default")
      (node (ref "PAD1") (pin "1") (pinfunction "SMD_Pad_1") (pintype "unspecified"))
    )
    (net (code "74") (name "unconnected-(PAD2-SMD_Pad-Pad1)") (class "Default")
      (node (ref "PAD2") (pin "1") (pinfunction "SMD_Pad_1") (pintype "unspecified"))
    )
    (net (code "75") (name "unconnected-(PAD3-SMD_Pad-Pad1)") (class "Default")
      (node (ref "PAD3") (pin "1") (pinfunction "SMD_Pad_1") (pintype "unspecified"))
    )
    (net (code "76") (name "unconnected-(PAD4-SMD_Pad-Pad1)") (class "Default")
      (node (ref "PAD4") (pin "1") (pinfunction "SMD_Pad_1") (pintype "unspecified"))
    )
    (net (code "77") (name "unconnected-(PAD5-SMD_Pad-Pad1)") (class "Default")
      (node (ref "PAD5") (pin "1") (pinfunction "SMD_Pad_1") (pintype "unspecified"))
    )
    (net (code "78") (name "unconnected-(PAD8-SMD_Pad-Pad1)") (class "Default")
      (node (ref "PAD8") (pin "1") (pinfunction "SMD_Pad_1") (pintype "unspecified"))
    )
    (net (code "79") (name "unconnected-(PAD9-SMD_Pad-Pad1)") (class "Default")
      (node (ref "PAD9") (pin "1") (pinfunction "SMD_Pad_1") (pintype "unspecified"))
    )
    (net (code "80") (name "unconnected-(PAD10-SMD_Pad-Pad1)") (class "Default")
      (node (ref "PAD10") (pin "1") (pinfunction "SMD_Pad_1") (pintype "unspecified"))
    )
    (net (code "81") (name "unconnected-(PAD11-SMD_Pad-Pad1)") (class "Default")
      (node (ref "PAD11") (pin "1") (pinfunction "SMD_Pad_1") (pintype "unspecified"))
    )
    (net (code "82") (name "unconnected-(PAD12-SMD_Pad-Pad1)") (class "Default")
      (node (ref "PAD12") (pin "1") (pinfunction "SMD_Pad_1") (pintype "unspecified"))
    )
    (net (code "83") (name "unconnected-(PAD13-SMD_Pad-Pad1)") (class "Default")
      (node (ref "PAD13") (pin "1") (pinfunction "SMD_Pad_1") (pintype "unspecified"))
    )
    (net (code "84") (name "unconnected-(PAD14-SMD_Pad-Pad1)") (class "Default")
      (node (ref "PAD14") (pin "1") (pinfunction "SMD_Pad_1") (pintype "unspecified"))
    )
    (net (code "85") (name "unconnected-(PAD15-SMD_Pad-Pad1)") (class "Default")
      (node (ref "PAD15") (pin "1") (pinfunction "SMD_Pad_1") (pintype "unspecified"))
    )
    (net (code "86") (name "unconnected-(PAD16-SMD_Pad-Pad1)") (class "Default")
      (node (ref "PAD16") (pin "1") (pinfunction "SMD_Pad_1") (pintype "unspecified"))
    )
    (net (code "87") (name "unconnected-(PAD17-SMD_Pad-Pad1)") (class "Default")
      (node (ref "PAD17") (pin "1") (pinfunction "SMD_Pad_1") (pintype "unspecified"))
    )
    (net (code "88") (name "unconnected-(PAD19-SMD_Pad-Pad1)") (class "Default")
      (node (ref "PAD19") (pin "1") (pinfunction "SMD_Pad_1") (pintype "unspecified"))
    )
    (net (code "89") (name "unconnected-(PAD20-SMD_Pad-Pad1)") (class "Default")
      (node (ref "PAD20") (pin "1") (pinfunction "SMD_Pad_1") (pintype "unspecified"))
    )
    (net (code "90") (name "unconnected-(PAD21-SMD_Pad-Pad1)") (class "Default")
      (node (ref "PAD21") (pin "1") (pinfunction "SMD_Pad_1") (pintype "unspecified"))
    )
    (net (code "91") (name "unconnected-(PAD22-SMD_Pad-Pad1)") (class "Default")
      (node (ref "PAD22") (pin "1") (pinfunction "SMD_Pad_1") (pintype "unspecified"))
    )
    (net (code "92") (name "unconnected-(PAD23-SMD_Pad-Pad1)") (class "Default")
      (node (ref "PAD23") (pin "1") (pinfunction "SMD_Pad_1") (pintype "unspecified"))
    )
    (net (code "93") (name "unconnected-(PAD25-SMD_Pad-Pad1)") (class "Default")
      (node (ref "PAD25") (pin "1") (pinfunction "SMD_Pad_1") (pintype "unspecified"))
    )
    (net (code "94") (name "unconnected-(PAD26-SMD_Pad-Pad1)") (class "Default")
      (node (ref "PAD26") (pin "1") (pinfunction "SMD_Pad_1") (pintype "unspecified"))
    )
    (net (code "95") (name "unconnected-(PAD27-SMD_Pad-Pad1)") (class "Default")
      (node (ref "PAD27") (pin "1") (pinfunction "SMD_Pad_1") (pintype "unspecified"))
    )
    (net (code "96") (name "unconnected-(PAD28-SMD_Pad-Pad1)") (class "Default")
      (node (ref "PAD28") (pin "1") (pinfunction "SMD_Pad_1") (pintype "unspecified"))
    )
    (net (code "97") (name "unconnected-(PAD29-SMD_Pad-Pad1)") (class "Default")
      (node (ref "PAD29") (pin "1") (pinfunction "SMD_Pad_1") (pintype "unspecified"))
    )
    (net (code "98") (name "unconnected-(PAD31-SMD_Pad-Pad1)") (class "Default")
      (node (ref "PAD31") (pin "1") (pinfunction "SMD_Pad_1") (pintype "unspecified"))
    )
    (net (code "99") (name "unconnected-(PAD32-SMD_Pad-Pad1)") (class "Default")
      (node (ref "PAD32") (pin "1") (pinfunction "SMD_Pad_1") (pintype "unspecified"))
    )
    (net (code "100") (name "unconnected-(PAD33-SMD_Pad-Pad1)") (class "Default")
      (node (ref "PAD33") (pin "1") (pinfunction "SMD_Pad_1") (pintype "unspecified"))
    )
    (net (code "101") (name "unconnected-(PAD34-SMD_Pad-Pad1)") (class "Default")
      (node (ref "PAD34") (pin "1") (pinfunction "SMD_Pad_1") (pintype "unspecified"))
    )
    (net (code "102") (name "unconnected-(PAD35-SMD_Pad-Pad1)") (class "Default")
      (node (ref "PAD35") (pin "1") (pinfunction "SMD_Pad_1") (pintype "unspecified"))
    )
    (net (code "103") (name "unconnected-(POTATO-EH-Pad4)") (class "Default")
      (node (ref "POTATO") (pin "4") (pinfunction "EH_4") (pintype "unspecified"))
    )
    (net (code "104") (name "unconnected-(POTATO-EH-Pad5)") (class "Default")
      (node (ref "POTATO") (pin "5") (pinfunction "EH_5") (pintype "unspecified"))
    )
    (net (code "105") (name "unconnected-(POTHEAD-EH-Pad4)") (class "Default")
      (node (ref "POTHEAD") (pin "4") (pinfunction "EH_4") (pintype "unspecified"))
    )
    (net (code "106") (name "unconnected-(POTHEAD-EH-Pad5)") (class "Default")
      (node (ref "POTHEAD") (pin "5") (pinfunction "EH_5") (pintype "unspecified"))
    )
    (net (code "107") (name "unconnected-(POTKNEES-EH-Pad4)") (class "Default")
      (node (ref "POTKNEES") (pin "4") (pinfunction "EH_4") (pintype "unspecified"))
    )
    (net (code "108") (name "unconnected-(POTKNEES-EH-Pad5)") (class "Default")
      (node (ref "POTKNEES") (pin "5") (pinfunction "EH_5") (pintype "unspecified"))
    )
    (net (code "109") (name "unconnected-(POTSHOULDERS-EH-Pad4)") (class "Default")
      (node (ref "POTSHOULDERS") (pin "4") (pinfunction "EH_4") (pintype "unspecified"))
    )
    (net (code "110") (name "unconnected-(POTSHOULDERS-EH-Pad5)") (class "Default")
      (node (ref "POTSHOULDERS") (pin "5") (pinfunction "EH_5") (pintype "unspecified"))
    )
    (net (code "111") (name "unconnected-(POTTER-EH-Pad4)") (class "Default")
      (node (ref "POTTER") (pin "4") (pinfunction "EH_4") (pintype "unspecified"))
    )
    (net (code "112") (name "unconnected-(POTTER-EH-Pad5)") (class "Default")
      (node (ref "POTTER") (pin "5") (pinfunction "EH_5") (pintype "unspecified"))
    )
    (net (code "113") (name "unconnected-(POTTOES-EH-Pad4)") (class "Default")
      (node (ref "POTTOES") (pin "4") (pinfunction "EH_4") (pintype "unspecified"))
    )
    (net (code "114") (name "unconnected-(POTTOES-EH-Pad5)") (class "Default")
      (node (ref "POTTOES") (pin "5") (pinfunction "EH_5") (pintype "unspecified"))
    )
  )
)
